# untitled.net
KiCad netlist of a schematic drawn in EAGLE
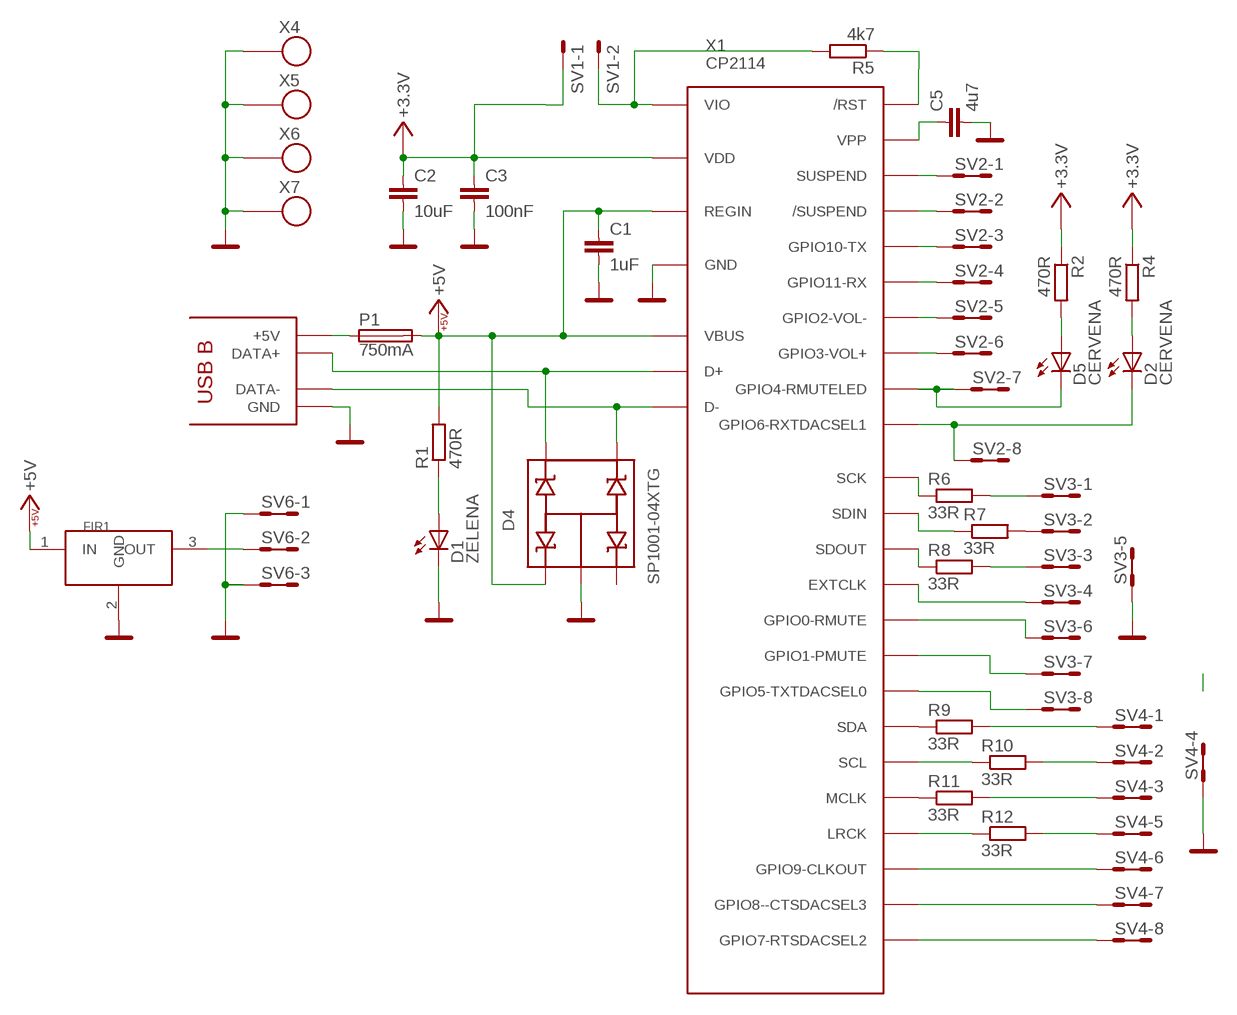
[diagram p0: schematic, sheet 1]

(export (version "E")
  (design (tool "Eeschema 10.0.6"))
  (components
    (comp (ref "C1")
      (value "1uF")
      (footprint "eagle-import:C0805")
      (libsource (lib "eagle-import") (part "C0805"))
    )
    (comp (ref "C2")
      (value "10uF")
      (footprint "eagle-import:C0805")
      (libsource (lib "eagle-import") (part "C0805"))
    )
    (comp (ref "C3")
      (value "100nF")
      (footprint "eagle-import:C0805")
      (libsource (lib "eagle-import") (part "C0805"))
    )
    (comp (ref "C5")
      (value "4u7")
      (footprint "eagle-import:C0805")
      (libsource (lib "eagle-import") (part "C0805"))
    )
    (comp (ref "D1")
      (value "ZELENA")
      (footprint "eagle-import:1206_2")
      (libsource (lib "eagle-import") (part "LED1206_2"))
    )
    (comp (ref "D2")
      (value "CERVENA")
      (footprint "eagle-import:1206_2")
      (libsource (lib "eagle-import") (part "LED1206_2"))
    )
    (comp (ref "D4")
      (value "SP1001-04XTG")
      (footprint "eagle-import:SOT553")
      (libsource (lib "eagle-import") (part "CP2112"))
    )
    (comp (ref "D5")
      (value "CERVENA")
      (footprint "eagle-import:1206_2")
      (libsource (lib "eagle-import") (part "LED1206_2"))
    )
    (comp (ref "FIR1")
      (value "FILTR0805")
      (footprint "eagle-import:F0805")
      (libsource (lib "eagle-import") (part "FILTR0805"))
    )
    (comp (ref "P1")
      (value "750mA")
      (footprint "eagle-import:1812")
      (libsource (lib "eagle-import") (part "POJISTKA_1812"))
    )
    (comp (ref "R1")
      (value "470R")
      (footprint "eagle-import:0805")
      (libsource (lib "eagle-import") (part "R0805"))
    )
    (comp (ref "R2")
      (value "470R")
      (footprint "eagle-import:0805")
      (libsource (lib "eagle-import") (part "R0805"))
    )
    (comp (ref "R4")
      (value "470R")
      (footprint "eagle-import:0805")
      (libsource (lib "eagle-import") (part "R0805"))
    )
    (comp (ref "R5")
      (value "4k7")
      (footprint "eagle-import:0805")
      (libsource (lib "eagle-import") (part "R0805"))
    )
    (comp (ref "R6")
      (value "33R")
      (footprint "eagle-import:0805")
      (libsource (lib "eagle-import") (part "R0805"))
    )
    (comp (ref "R7")
      (value "33R")
      (footprint "eagle-import:0805")
      (libsource (lib "eagle-import") (part "R0805"))
    )
    (comp (ref "R8")
      (value "33R")
      (footprint "eagle-import:0805")
      (libsource (lib "eagle-import") (part "R0805"))
    )
    (comp (ref "R9")
      (value "33R")
      (footprint "eagle-import:0805")
      (libsource (lib "eagle-import") (part "R0805"))
    )
    (comp (ref "R10")
      (value "33R")
      (footprint "eagle-import:0805")
      (libsource (lib "eagle-import") (part "R0805"))
    )
    (comp (ref "R11")
      (value "33R")
      (footprint "eagle-import:0805")
      (libsource (lib "eagle-import") (part "R0805"))
    )
    (comp (ref "R12")
      (value "33R")
      (footprint "eagle-import:0805")
      (libsource (lib "eagle-import") (part "R0805"))
    )
    (comp (ref "SV1")
      (value "MA02-1")
      (footprint "eagle-import:MA02-1")
      (libsource (lib "eagle-import") (part "MA02-1"))
    )
    (comp (ref "SV2")
      (value "MA08-2")
      (footprint "eagle-import:MA08-2")
      (libsource (lib "eagle-import") (part "MA08-2"))
    )
    (comp (ref "SV3")
      (value "MA08-2")
      (footprint "eagle-import:MA08-2")
      (libsource (lib "eagle-import") (part "MA08-2"))
    )
    (comp (ref "SV4")
      (value "MA08-2")
      (footprint "eagle-import:MA08-2")
      (libsource (lib "eagle-import") (part "MA08-2"))
    )
    (comp (ref "SV6")
      (value "MA03-2")
      (footprint "eagle-import:MA03-2")
      (libsource (lib "eagle-import") (part "MA03-2"))
    )
    (comp (ref "X1")
      (value "CP2114")
      (footprint "eagle-import:QFN-32")
      (libsource (lib "eagle-import") (part "CP2114"))
    )
    (comp (ref "X3")
      (value "USB_B")
      (footprint "eagle-import:USB_B")
      (libsource (lib "eagle-import") (part "USB_B"))
    )
    (comp (ref "X4")
      (value "SROUB3M")
      (footprint "eagle-import:SROUB3M")
      (libsource (lib "eagle-import") (part "SROUB3M"))
    )
    (comp (ref "X5")
      (value "SROUB3M")
      (footprint "eagle-import:SROUB3M")
      (libsource (lib "eagle-import") (part "SROUB3M"))
    )
    (comp (ref "X6")
      (value "SROUB3M")
      (footprint "eagle-import:SROUB3M")
      (libsource (lib "eagle-import") (part "SROUB3M"))
    )
    (comp (ref "X7")
      (value "SROUB3M")
      (footprint "eagle-import:SROUB3M")
      (libsource (lib "eagle-import") (part "SROUB3M"))
    )
  )
  (nets
    (net (code "1") (name "+3.3V") (class "Default")
      (node (ref "C2") (pin "1") (pinfunction "1_1") (pintype "passive"))
      (node (ref "C3") (pin "1") (pinfunction "1_1") (pintype "passive"))
      (node (ref "R2") (pin "1") (pinfunction "1_1") (pintype "passive"))
      (node (ref "R4") (pin "1") (pinfunction "1_1") (pintype "passive"))
      (node (ref "SV1") (pin "1") (pinfunction "P$1_1") (pintype "passive"))
      (node (ref "X1") (pin "7") (pinfunction "VDD_7") (pintype "bidirectional"))
    )
    (net (code "2") (name "+5V") (class "Default")
      (node (ref "C1") (pin "1") (pinfunction "1_1") (pintype "passive"))
      (node (ref "D4") (pin "1") (pinfunction "P$1_1") (pintype "passive"))
      (node (ref "FIR1") (pin "1") (pinfunction "IN_1") (pintype "bidirectional"))
      (node (ref "P1") (pin "2") (pinfunction "2_2") (pintype "passive"))
      (node (ref "R1") (pin "2") (pinfunction "2_2") (pintype "passive"))
      (node (ref "X1") (pin "8") (pinfunction "REGIN_8") (pintype "bidirectional"))
      (node (ref "X1") (pin "9") (pinfunction "VBUS_9") (pintype "bidirectional"))
    )
    (net (code "3") (name "GND") (class "Default")
      (node (ref "C1") (pin "2") (pinfunction "2_2") (pintype "passive"))
      (node (ref "C2") (pin "2") (pinfunction "2_2") (pintype "passive"))
      (node (ref "C3") (pin "2") (pinfunction "2_2") (pintype "passive"))
      (node (ref "C5") (pin "2") (pinfunction "2_2") (pintype "passive"))
      (node (ref "D1") (pin "K") (pinfunction "C_K") (pintype "passive"))
      (node (ref "D4") (pin "2") (pinfunction "P$2_2") (pintype "passive"))
      (node (ref "FIR1") (pin "2") (pinfunction "GND_2") (pintype "passive"))
      (node (ref "SV3") (pin "10") (pinfunction "K_10") (pintype "passive"))
      (node (ref "SV3") (pin "9") (pinfunction "K_9") (pintype "passive"))
      (node (ref "SV4") (pin "7") (pinfunction "K_7") (pintype "passive"))
      (node (ref "SV4") (pin "8") (pinfunction "K_8") (pintype "passive"))
      (node (ref "SV6") (pin "1") (pinfunction "K_1") (pintype "passive"))
      (node (ref "SV6") (pin "2") (pinfunction "K_2") (pintype "passive"))
      (node (ref "SV6") (pin "5") (pinfunction "K_5") (pintype "passive"))
      (node (ref "SV6") (pin "6") (pinfunction "K_6") (pintype "passive"))
      (node (ref "X1") (pin "3") (pinfunction "GND_3") (pintype "bidirectional"))
      (node (ref "X1") (pin "EXP") (pinfunction "GND_EXP") (pintype "bidirectional"))
      (node (ref "X3") (pin "4") (pinfunction "GND_4") (pintype "bidirectional"))
      (node (ref "X3") (pin "GND") (pinfunction "GND_GND") (pintype "bidirectional"))
      (node (ref "X3") (pin "GND2") (pinfunction "GND_GND2") (pintype "bidirectional"))
      (node (ref "X4") (pin "P$1") (pinfunction "P$1_P$1") (pintype "bidirectional"))
      (node (ref "X5") (pin "P$1") (pinfunction "P$1_P$1") (pintype "bidirectional"))
      (node (ref "X6") (pin "P$1") (pinfunction "P$1_P$1") (pintype "bidirectional"))
      (node (ref "X7") (pin "P$1") (pinfunction "P$1_P$1") (pintype "bidirectional"))
    )
    (net (code "4") (name "Net-(D1-PadA)") (class "Default")
      (node (ref "D1") (pin "A") (pinfunction "A_A") (pintype "passive"))
      (node (ref "R1") (pin "1") (pinfunction "1_1") (pintype "passive"))
    )
    (net (code "5") (name "Net-(D2-C)") (class "Default")
      (node (ref "D2") (pin "K") (pinfunction "C_K") (pintype "passive"))
      (node (ref "SV2") (pin "15") (pinfunction "K_15") (pintype "passive"))
      (node (ref "SV2") (pin "16") (pinfunction "K_16") (pintype "passive"))
      (node (ref "X1") (pin "11") (pinfunction "GPIO6-RXTDACSEL1_11") (pintype "bidirectional"))
    )
    (net (code "6") (name "Net-(D2-PadA)") (class "Default")
      (node (ref "D2") (pin "A") (pinfunction "A_A") (pintype "passive"))
      (node (ref "R4") (pin "2") (pinfunction "2_2") (pintype "passive"))
    )
    (net (code "7") (name "Net-(D4-P$4)") (class "Default")
      (node (ref "D4") (pin "4") (pinfunction "P$4_4") (pintype "passive"))
      (node (ref "X1") (pin "5") (pinfunction "D-_5") (pintype "bidirectional"))
      (node (ref "X3") (pin "2") (pinfunction "DATA-_2") (pintype "bidirectional"))
    )
    (net (code "8") (name "Net-(D4-P$5)") (class "Default")
      (node (ref "D4") (pin "5") (pinfunction "P$5_5") (pintype "passive"))
      (node (ref "X1") (pin "4") (pinfunction "D+_4") (pintype "bidirectional"))
      (node (ref "X3") (pin "3") (pinfunction "DATA+_3") (pintype "bidirectional"))
    )
    (net (code "9") (name "Net-(D5-C)") (class "Default")
      (node (ref "D5") (pin "K") (pinfunction "C_K") (pintype "passive"))
      (node (ref "SV2") (pin "13") (pinfunction "K_13") (pintype "passive"))
      (node (ref "SV2") (pin "14") (pinfunction "K_14") (pintype "passive"))
      (node (ref "X1") (pin "12") (pinfunction "GPIO4-RMUTELED_12") (pintype "bidirectional"))
    )
    (net (code "10") (name "Net-(D5-PadA)") (class "Default")
      (node (ref "D5") (pin "A") (pinfunction "A_A") (pintype "passive"))
      (node (ref "R2") (pin "2") (pinfunction "2_2") (pintype "passive"))
    )
    (net (code "11") (name "Net-(FIR1-OUT)") (class "Default")
      (node (ref "FIR1") (pin "3") (pinfunction "OUT_3") (pintype "bidirectional"))
      (node (ref "SV6") (pin "3") (pinfunction "K_3") (pintype "passive"))
      (node (ref "SV6") (pin "4") (pinfunction "K_4") (pintype "passive"))
    )
    (net (code "12") (name "Net-(R6-Pad2)") (class "Default")
      (node (ref "R6") (pin "2") (pinfunction "2_2") (pintype "passive"))
      (node (ref "SV3") (pin "1") (pinfunction "K_1") (pintype "passive"))
      (node (ref "SV3") (pin "2") (pinfunction "K_2") (pintype "passive"))
    )
    (net (code "13") (name "Net-(R7-Pad2)") (class "Default")
      (node (ref "R7") (pin "2") (pinfunction "2_2") (pintype "passive"))
      (node (ref "SV3") (pin "3") (pinfunction "K_3") (pintype "passive"))
      (node (ref "SV3") (pin "4") (pinfunction "K_4") (pintype "passive"))
    )
    (net (code "14") (name "Net-(R8-Pad2)") (class "Default")
      (node (ref "R8") (pin "2") (pinfunction "2_2") (pintype "passive"))
      (node (ref "SV3") (pin "5") (pinfunction "K_5") (pintype "passive"))
      (node (ref "SV3") (pin "6") (pinfunction "K_6") (pintype "passive"))
    )
    (net (code "15") (name "Net-(R9-Pad2)") (class "Default")
      (node (ref "R9") (pin "2") (pinfunction "2_2") (pintype "passive"))
      (node (ref "SV4") (pin "1") (pinfunction "K_1") (pintype "passive"))
      (node (ref "SV4") (pin "2") (pinfunction "K_2") (pintype "passive"))
    )
    (net (code "16") (name "Net-(R10-Pad2)") (class "Default")
      (node (ref "R10") (pin "2") (pinfunction "2_2") (pintype "passive"))
      (node (ref "SV4") (pin "3") (pinfunction "K_3") (pintype "passive"))
      (node (ref "SV4") (pin "4") (pinfunction "K_4") (pintype "passive"))
    )
    (net (code "17") (name "Net-(R11-Pad2)") (class "Default")
      (node (ref "R11") (pin "2") (pinfunction "2_2") (pintype "passive"))
      (node (ref "SV4") (pin "5") (pinfunction "K_5") (pintype "passive"))
      (node (ref "SV4") (pin "6") (pinfunction "K_6") (pintype "passive"))
    )
    (net (code "18") (name "Net-(R12-Pad2)") (class "Default")
      (node (ref "R12") (pin "2") (pinfunction "2_2") (pintype "passive"))
      (node (ref "SV4") (pin "10") (pinfunction "K_10") (pintype "passive"))
      (node (ref "SV4") (pin "9") (pinfunction "K_9") (pintype "passive"))
    )
    (net (code "19") (name "Net-(SV1B-P$1)") (class "Default")
      (node (ref "R5") (pin "2") (pinfunction "2_2") (pintype "passive"))
      (node (ref "SV1") (pin "2") (pinfunction "P$1_2") (pintype "passive"))
      (node (ref "X1") (pin "6") (pinfunction "VIO_6") (pintype "bidirectional"))
    )
    (net (code "20") (name "Net-(X1-EXTCLK)") (class "Default")
      (node (ref "SV3") (pin "7") (pinfunction "K_7") (pintype "passive"))
      (node (ref "SV3") (pin "8") (pinfunction "K_8") (pintype "passive"))
      (node (ref "X1") (pin "31") (pinfunction "EXTCLK_31") (pintype "bidirectional"))
    )
    (net (code "21") (name "Net-(X1-GPIO0-RMUTE)") (class "Default")
      (node (ref "SV3") (pin "11") (pinfunction "K_11") (pintype "passive"))
      (node (ref "SV3") (pin "12") (pinfunction "K_12") (pintype "passive"))
      (node (ref "X1") (pin "30") (pinfunction "GPIO0-RMUTE_30") (pintype "bidirectional"))
    )
    (net (code "22") (name "Net-(X1-GPIO1-PMUTE)") (class "Default")
      (node (ref "SV3") (pin "13") (pinfunction "K_13") (pintype "passive"))
      (node (ref "SV3") (pin "14") (pinfunction "K_14") (pintype "passive"))
      (node (ref "X1") (pin "29") (pinfunction "GPIO1-PMUTE_29") (pintype "bidirectional"))
    )
    (net (code "23") (name "Net-(X1-GPIO2-VOL-)") (class "Default")
      (node (ref "SV2") (pin "10") (pinfunction "K_10") (pintype "passive"))
      (node (ref "SV2") (pin "9") (pinfunction "K_9") (pintype "passive"))
      (node (ref "X1") (pin "14") (pinfunction "GPIO2-VOL-_14") (pintype "bidirectional"))
    )
    (net (code "24") (name "Net-(X1-GPIO3-VOL+)") (class "Default")
      (node (ref "SV2") (pin "11") (pinfunction "K_11") (pintype "passive"))
      (node (ref "SV2") (pin "12") (pinfunction "K_12") (pintype "passive"))
      (node (ref "X1") (pin "13") (pinfunction "GPIO3-VOL+_13") (pintype "bidirectional"))
    )
    (net (code "25") (name "Net-(X1-GPIO5-TXTDACSEL0)") (class "Default")
      (node (ref "SV3") (pin "15") (pinfunction "K_15") (pintype "passive"))
      (node (ref "SV3") (pin "16") (pinfunction "K_16") (pintype "passive"))
      (node (ref "X1") (pin "28") (pinfunction "GPIO5-TXTDACSEL0_28") (pintype "bidirectional"))
    )
    (net (code "26") (name "Net-(X1-GPIO7-RTSDACSEL2)") (class "Default")
      (node (ref "SV4") (pin "15") (pinfunction "K_15") (pintype "passive"))
      (node (ref "SV4") (pin "16") (pinfunction "K_16") (pintype "passive"))
      (node (ref "X1") (pin "19") (pinfunction "GPIO7-RTSDACSEL2_19") (pintype "bidirectional"))
    )
    (net (code "27") (name "Net-(X1-GPIO8--CTSDACSEL3)") (class "Default")
      (node (ref "SV4") (pin "13") (pinfunction "K_13") (pintype "passive"))
      (node (ref "SV4") (pin "14") (pinfunction "K_14") (pintype "passive"))
      (node (ref "X1") (pin "20") (pinfunction "GPIO8--CTSDACSEL3_20") (pintype "bidirectional"))
    )
    (net (code "28") (name "Net-(X1-GPIO9-CLKOUT)") (class "Default")
      (node (ref "SV4") (pin "11") (pinfunction "K_11") (pintype "passive"))
      (node (ref "SV4") (pin "12") (pinfunction "K_12") (pintype "passive"))
      (node (ref "X1") (pin "22") (pinfunction "GPIO9-CLKOUT_22") (pintype "bidirectional"))
    )
    (net (code "29") (name "Net-(X1-GPIO10-TX)") (class "Default")
      (node (ref "SV2") (pin "5") (pinfunction "K_5") (pintype "passive"))
      (node (ref "SV2") (pin "6") (pinfunction "K_6") (pintype "passive"))
      (node (ref "X1") (pin "16") (pinfunction "GPIO10-TX_16") (pintype "bidirectional"))
    )
    (net (code "30") (name "Net-(X1-GPIO11-RX)") (class "Default")
      (node (ref "SV2") (pin "7") (pinfunction "K_7") (pintype "passive"))
      (node (ref "SV2") (pin "8") (pinfunction "K_8") (pintype "passive"))
      (node (ref "X1") (pin "15") (pinfunction "GPIO11-RX_15") (pintype "bidirectional"))
    )
    (net (code "31") (name "Net-(X1-LRCK)") (class "Default")
      (node (ref "R12") (pin "1") (pinfunction "1_1") (pintype "passive"))
      (node (ref "X1") (pin "23") (pinfunction "LRCK_23") (pintype "bidirectional"))
    )
    (net (code "32") (name "Net-(X1-MCLK)") (class "Default")
      (node (ref "R11") (pin "1") (pinfunction "1_1") (pintype "passive"))
      (node (ref "X1") (pin "25") (pinfunction "MCLK_25") (pintype "bidirectional"))
    )
    (net (code "33") (name "Net-(X1-SCK)") (class "Default")
      (node (ref "R6") (pin "1") (pinfunction "1_1") (pintype "passive"))
      (node (ref "X1") (pin "2") (pinfunction "SCK_2") (pintype "bidirectional"))
    )
    (net (code "34") (name "Net-(X1-SCL)") (class "Default")
      (node (ref "R10") (pin "1") (pinfunction "1_1") (pintype "passive"))
      (node (ref "X1") (pin "26") (pinfunction "SCL_26") (pintype "bidirectional"))
    )
    (net (code "35") (name "Net-(X1-SDA)") (class "Default")
      (node (ref "R9") (pin "1") (pinfunction "1_1") (pintype "passive"))
      (node (ref "X1") (pin "27") (pinfunction "SDA_27") (pintype "bidirectional"))
    )
    (net (code "36") (name "Net-(X1-SDIN)") (class "Default")
      (node (ref "R7") (pin "1") (pinfunction "1_1") (pintype "passive"))
      (node (ref "X1") (pin "1") (pinfunction "SDIN_1") (pintype "bidirectional"))
    )
    (net (code "37") (name "Net-(X1-SDOUT)") (class "Default")
      (node (ref "R8") (pin "1") (pinfunction "1_1") (pintype "passive"))
      (node (ref "X1") (pin "32") (pinfunction "SDOUT_32") (pintype "bidirectional"))
    )
    (net (code "38") (name "Net-(X1-SUSPEND)") (class "Default")
      (node (ref "SV2") (pin "1") (pinfunction "K_1") (pintype "passive"))
      (node (ref "SV2") (pin "2") (pinfunction "K_2") (pintype "passive"))
      (node (ref "X1") (pin "18") (pinfunction "SUSPEND_18") (pintype "bidirectional"))
    )
    (net (code "39") (name "Net-(X1-VPP)") (class "Default")
      (node (ref "C5") (pin "1") (pinfunction "1_1") (pintype "passive"))
      (node (ref "X1") (pin "21") (pinfunction "VPP_21") (pintype "bidirectional"))
    )
    (net (code "40") (name "Net-(X1-{slash}RST)") (class "Default")
      (node (ref "R5") (pin "1") (pinfunction "1_1") (pintype "passive"))
      (node (ref "X1") (pin "10") (pinfunction "/RST_10") (pintype "bidirectional"))
    )
    (net (code "41") (name "Net-(X1-{slash}SUSPEND)") (class "Default")
      (node (ref "SV2") (pin "3") (pinfunction "K_3") (pintype "passive"))
      (node (ref "SV2") (pin "4") (pinfunction "K_4") (pintype "passive"))
      (node (ref "X1") (pin "17") (pinfunction "/SUSPEND_17") (pintype "bidirectional"))
    )
    (net (code "42") (name "Net-(X3-+5V)") (class "Default")
      (node (ref "P1") (pin "1") (pinfunction "1_1") (pintype "passive"))
      (node (ref "X3") (pin "1") (pinfunction "+5V_1") (pintype "bidirectional"))
    )
    (net (code "43") (name "unconnected-(D4-P$3-Pad3)") (class "Default")
      (node (ref "D4") (pin "3") (pinfunction "P$3_3") (pintype "passive"))
    )
  )
)
